# QFN-24_4x4mm_Breakout.net
KiCad netlist of a schematic drawn in EAGLE
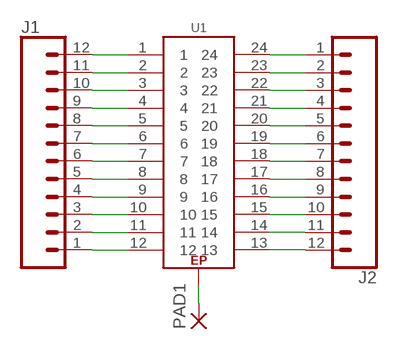
[diagram p0: schematic, sheet 1]

(export (version "E")
  (design (tool "Eeschema 10.0.6"))
  (components
    (comp (ref "J1")
      (value "CONN_12")
      (footprint "eagle-import:1X12")
      (libsource (lib "eagle-import") (part "CONN_12"))
    )
    (comp (ref "J2")
      (value "CONN_12")
      (footprint "eagle-import:1X12")
      (libsource (lib "eagle-import") (part "CONN_12"))
    )
    (comp (ref "PAD1")
      (value "SMD2")
      (footprint "eagle-import:SMD1,27-2,54")
      (fields (field (name "MPN") "DNP"))
      (libsource (lib "eagle-import") (part "SMD2"))
    )
    (comp (ref "U1")
      (value "GEN_24_EPQFN-24")
      (footprint "eagle-import:QFN24")
      (libsource (lib "eagle-import") (part "GEN_24_EPQFN-24"))
    )
  )
  (nets
    (net (code "1") (name "Net-(J1-Pad1)") (class "Default")
      (node (ref "J1") (pin "1") (pinfunction "1_1") (pintype "passive"))
      (node (ref "U1") (pin "12") (pinfunction "12_12") (pintype "bidirectional"))
    )
    (net (code "2") (name "Net-(J1-Pad2)") (class "Default")
      (node (ref "J1") (pin "2") (pinfunction "2_2") (pintype "passive"))
      (node (ref "U1") (pin "11") (pinfunction "11_11") (pintype "bidirectional"))
    )
    (net (code "3") (name "Net-(J1-Pad3)") (class "Default")
      (node (ref "J1") (pin "3") (pinfunction "3_3") (pintype "passive"))
      (node (ref "U1") (pin "10") (pinfunction "10_10") (pintype "bidirectional"))
    )
    (net (code "4") (name "Net-(J1-Pad4)") (class "Default")
      (node (ref "J1") (pin "4") (pinfunction "4_4") (pintype "passive"))
      (node (ref "U1") (pin "9") (pinfunction "9_9") (pintype "bidirectional"))
    )
    (net (code "5") (name "Net-(J1-Pad5)") (class "Default")
      (node (ref "J1") (pin "5") (pinfunction "5_5") (pintype "passive"))
      (node (ref "U1") (pin "8") (pinfunction "8_8") (pintype "bidirectional"))
    )
    (net (code "6") (name "Net-(J1-Pad6)") (class "Default")
      (node (ref "J1") (pin "6") (pinfunction "6_6") (pintype "passive"))
      (node (ref "U1") (pin "7") (pinfunction "7_7") (pintype "bidirectional"))
    )
    (net (code "7") (name "Net-(J1-Pad7)") (class "Default")
      (node (ref "J1") (pin "7") (pinfunction "7_7") (pintype "passive"))
      (node (ref "U1") (pin "6") (pinfunction "6_6") (pintype "bidirectional"))
    )
    (net (code "8") (name "Net-(J1-Pad8)") (class "Default")
      (node (ref "J1") (pin "8") (pinfunction "8_8") (pintype "passive"))
      (node (ref "U1") (pin "5") (pinfunction "5_5") (pintype "bidirectional"))
    )
    (net (code "9") (name "Net-(J1-Pad9)") (class "Default")
      (node (ref "J1") (pin "9") (pinfunction "9_9") (pintype "passive"))
      (node (ref "U1") (pin "4") (pinfunction "4_4") (pintype "bidirectional"))
    )
    (net (code "10") (name "Net-(J1-Pad10)") (class "Default")
      (node (ref "J1") (pin "10") (pinfunction "10_10") (pintype "passive"))
      (node (ref "U1") (pin "3") (pinfunction "3_3") (pintype "bidirectional"))
    )
    (net (code "11") (name "Net-(J1-Pad11)") (class "Default")
      (node (ref "J1") (pin "11") (pinfunction "11_11") (pintype "passive"))
      (node (ref "U1") (pin "2") (pinfunction "2_2") (pintype "bidirectional"))
    )
    (net (code "12") (name "Net-(J1-Pad12)") (class "Default")
      (node (ref "J1") (pin "12") (pinfunction "12_12") (pintype "passive"))
      (node (ref "U1") (pin "1") (pinfunction "1_1") (pintype "bidirectional"))
    )
    (net (code "13") (name "Net-(J2-Pad1)") (class "Default")
      (node (ref "J2") (pin "1") (pinfunction "1_1") (pintype "passive"))
      (node (ref "U1") (pin "24") (pinfunction "24_24") (pintype "bidirectional"))
    )
    (net (code "14") (name "Net-(J2-Pad2)") (class "Default")
      (node (ref "J2") (pin "2") (pinfunction "2_2") (pintype "passive"))
      (node (ref "U1") (pin "23") (pinfunction "23_23") (pintype "bidirectional"))
    )
    (net (code "15") (name "Net-(J2-Pad3)") (class "Default")
      (node (ref "J2") (pin "3") (pinfunction "3_3") (pintype "passive"))
      (node (ref "U1") (pin "22") (pinfunction "22_22") (pintype "bidirectional"))
    )
    (net (code "16") (name "Net-(J2-Pad4)") (class "Default")
      (node (ref "J2") (pin "4") (pinfunction "4_4") (pintype "passive"))
      (node (ref "U1") (pin "21") (pinfunction "21_21") (pintype "bidirectional"))
    )
    (net (code "17") (name "Net-(J2-Pad5)") (class "Default")
      (node (ref "J2") (pin "5") (pinfunction "5_5") (pintype "passive"))
      (node (ref "U1") (pin "20") (pinfunction "20_20") (pintype "bidirectional"))
    )
    (net (code "18") (name "Net-(J2-Pad6)") (class "Default")
      (node (ref "J2") (pin "6") (pinfunction "6_6") (pintype "passive"))
      (node (ref "U1") (pin "19") (pinfunction "19_19") (pintype "bidirectional"))
    )
    (net (code "19") (name "Net-(J2-Pad7)") (class "Default")
      (node (ref "J2") (pin "7") (pinfunction "7_7") (pintype "passive"))
      (node (ref "U1") (pin "18") (pinfunction "18_18") (pintype "bidirectional"))
    )
    (net (code "20") (name "Net-(J2-Pad8)") (class "Default")
      (node (ref "J2") (pin "8") (pinfunction "8_8") (pintype "passive"))
      (node (ref "U1") (pin "17") (pinfunction "17_17") (pintype "bidirectional"))
    )
    (net (code "21") (name "Net-(J2-Pad9)") (class "Default")
      (node (ref "J2") (pin "9") (pinfunction "9_9") (pintype "passive"))
      (node (ref "U1") (pin "16") (pinfunction "16_16") (pintype "bidirectional"))
    )
    (net (code "22") (name "Net-(J2-Pad10)") (class "Default")
      (node (ref "J2") (pin "10") (pinfunction "10_10") (pintype "passive"))
      (node (ref "U1") (pin "15") (pinfunction "15_15") (pintype "bidirectional"))
    )
    (net (code "23") (name "Net-(J2-Pad11)") (class "Default")
      (node (ref "J2") (pin "11") (pinfunction "11_11") (pintype "passive"))
      (node (ref "U1") (pin "14") (pinfunction "14_14") (pintype "bidirectional"))
    )
    (net (code "24") (name "Net-(J2-Pad12)") (class "Default")
      (node (ref "J2") (pin "12") (pinfunction "12_12") (pintype "passive"))
      (node (ref "U1") (pin "13") (pinfunction "13_13") (pintype "bidirectional"))
    )
    (net (code "25") (name "Net-(PAD1-P)") (class "Default")
      (node (ref "PAD1") (pin "1") (pinfunction "P_1") (pintype "passive"))
      (node (ref "U1") (pin "EP") (pinfunction "EP_EP") (pintype "passive"))
    )
  )
)
